# 20210419-JGaylord-doorman_adult_rig.net
KiCad netlist of a schematic drawn in EAGLE
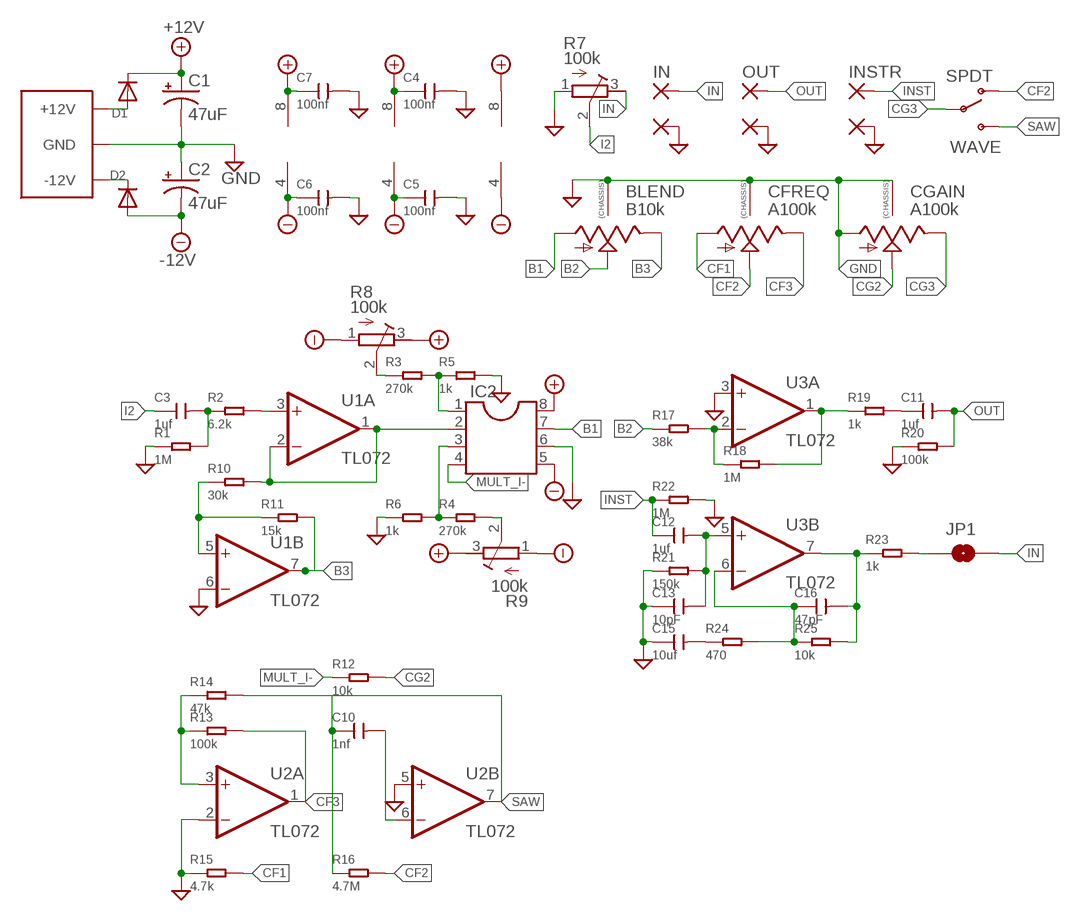
[diagram p0: schematic, sheet 1]

(export (version "E")
  (design (tool "Eeschema 10.0.6"))
  (components
    (comp (ref "BLEND")
      (value "B10k")
      (footprint "eagle-import:9MM_SNAP-IN_POT")
      (libsource (lib "eagle-import") (part "9MM_SNAP-IN_POT_CHASSIS"))
    )
    (comp (ref "C1")
      (value "47uF")
      (footprint "eagle-import:PAN_B_SMD+THRU")
      (libsource (lib "eagle-import") (part "CAP_SMD+THRUPAN_B"))
    )
    (comp (ref "C2")
      (value "47uF")
      (footprint "eagle-import:PAN_B_SMD+THRU")
      (libsource (lib "eagle-import") (part "CAP_SMD+THRUPAN_B"))
    )
    (comp (ref "C3")
      (value "1uf")
      (footprint "eagle-import:C1206")
      (fields (field (name "MPN") "CC1206KKX5R8BB106"))
      (libsource (lib "eagle-import") (part "CERAMIC-10UF-25V-10%-X5R(1206)"))
    )
    (comp (ref "C4")
      (value "100nf")
      (footprint "eagle-import:C0805")
      (fields (field (name "MPN") "CC0805KRX7R9BB104"))
      (libsource (lib "eagle-import") (part "CERAMIC-100NF-50V-10%-X7R(0805)"))
    )
    (comp (ref "C5")
      (value "100nf")
      (footprint "eagle-import:C0805")
      (fields (field (name "MPN") "CC0805KRX7R9BB104"))
      (libsource (lib "eagle-import") (part "CERAMIC-100NF-50V-10%-X7R(0805)"))
    )
    (comp (ref "C6")
      (value "100nf")
      (footprint "eagle-import:C0805")
      (fields (field (name "MPN") "CC0805KRX7R9BB104"))
      (libsource (lib "eagle-import") (part "CERAMIC-100NF-50V-10%-X7R(0805)"))
    )
    (comp (ref "C7")
      (value "100nf")
      (footprint "eagle-import:C0805")
      (fields (field (name "MPN") "CC0805KRX7R9BB104"))
      (libsource (lib "eagle-import") (part "CERAMIC-100NF-50V-10%-X7R(0805)"))
    )
    (comp (ref "C10")
      (value "1nf")
      (footprint "eagle-import:C0805")
      (fields (field (name "MPN") "CC0805KRX7R9BB104"))
      (libsource (lib "eagle-import") (part "CERAMIC-100NF-50V-10%-X7R(0805)"))
    )
    (comp (ref "C11")
      (value "1uf")
      (footprint "eagle-import:C1206")
      (fields (field (name "MPN") "CC1206KKX5R8BB106"))
      (libsource (lib "eagle-import") (part "CERAMIC-10UF-25V-10%-X5R(1206)"))
    )
    (comp (ref "C12")
      (value "1uf")
      (footprint "eagle-import:C1206")
      (fields (field (name "MPN") "CC1206KKX5R8BB106"))
      (libsource (lib "eagle-import") (part "CERAMIC-10UF-25V-10%-X5R(1206)"))
    )
    (comp (ref "C13")
      (value "10pF")
      (footprint "eagle-import:C0805")
      (fields (field (name "MPN") "CC0805KRX7R9BB104"))
      (libsource (lib "eagle-import") (part "CERAMIC-100NF-50V-10%-X7R(0805)"))
    )
    (comp (ref "C15")
      (value "10uf")
      (footprint "eagle-import:C1206")
      (fields (field (name "MPN") "CC1206KKX5R8BB106"))
      (libsource (lib "eagle-import") (part "CERAMIC-10UF-25V-10%-X5R(1206)"))
    )
    (comp (ref "C16")
      (value "47pF")
      (footprint "eagle-import:C0805")
      (fields (field (name "MPN") "CC0805KRX7R9BB104"))
      (libsource (lib "eagle-import") (part "CERAMIC-100NF-50V-10%-X7R(0805)"))
    )
    (comp (ref "CFREQ")
      (value "A100k")
      (footprint "eagle-import:9MM_SNAP-IN_POT")
      (libsource (lib "eagle-import") (part "9MM_SNAP-IN_POT_CHASSIS"))
    )
    (comp (ref "CGAIN")
      (value "A100k")
      (footprint "eagle-import:9MM_SNAP-IN_POT")
      (libsource (lib "eagle-import") (part "9MM_SNAP-IN_POT_CHASSIS"))
    )
    (comp (ref "D1")
      (value "DIODESOD-123")
      (footprint "eagle-import:SOD-123")
      (libsource (lib "eagle-import") (part "DIODESOD-123"))
    )
    (comp (ref "D2")
      (value "DIODESOD-123")
      (footprint "eagle-import:SOD-123")
      (libsource (lib "eagle-import") (part "DIODESOD-123"))
    )
    (comp (ref "GND")
      (value "WIREPAD1,6/0,9")
      (footprint "eagle-import:1,6_0,9")
      (libsource (lib "eagle-import") (part "WIREPAD1,6/0,9"))
    )
    (comp (ref "GND1")
      (value "WIREPAD1,6/0,9")
      (footprint "eagle-import:1,6_0,9")
      (libsource (lib "eagle-import") (part "WIREPAD1,6/0,9"))
    )
    (comp (ref "GND2")
      (value "WIREPAD1,6/0,9")
      (footprint "eagle-import:1,6_0,9")
      (libsource (lib "eagle-import") (part "WIREPAD1,6/0,9"))
    )
    (comp (ref "IC2")
      (value "DIL8")
      (footprint "eagle-import:DIL08")
      (libsource (lib "eagle-import") (part "DIL8"))
    )
    (comp (ref "IN")
      (value "WIREPAD1,6/0,9")
      (footprint "eagle-import:1,6_0,9")
      (libsource (lib "eagle-import") (part "WIREPAD1,6/0,9"))
    )
    (comp (ref "INSTR")
      (value "WIREPAD1,6/0,9")
      (footprint "eagle-import:1,6_0,9")
      (libsource (lib "eagle-import") (part "WIREPAD1,6/0,9"))
    )
    (comp (ref "JP1")
      (value "JUMPER-SMT_2_NO_NO-SILK")
      (footprint "eagle-import:SMT-JUMPER_2_NO_NO-SILK")
      (libsource (lib "eagle-import") (part "JUMPER-SMT_2_NO_NO-SILK"))
    )
    (comp (ref "OUT")
      (value "WIREPAD1,6/0,9")
      (footprint "eagle-import:1,6_0,9")
      (libsource (lib "eagle-import") (part "WIREPAD1,6/0,9"))
    )
    (comp (ref "R1")
      (value "1M")
      (footprint "eagle-import:R0805")
      (fields (field (name "MPN") "RC0805JR-071KL"))
      (libsource (lib "eagle-import") (part "SMD-RES-1K-5%-1/8W(0805)"))
    )
    (comp (ref "R2")
      (value "6.2k")
      (footprint "eagle-import:R0805")
      (fields (field (name "MPN") "RC0805JR-071KL"))
      (libsource (lib "eagle-import") (part "SMD-RES-1K-5%-1/8W(0805)"))
    )
    (comp (ref "R3")
      (value "270k")
      (footprint "eagle-import:R0805")
      (fields (field (name "MPN") "RC0805JR-071KL"))
      (libsource (lib "eagle-import") (part "SMD-RES-1K-5%-1/8W(0805)"))
    )
    (comp (ref "R4")
      (value "270k")
      (footprint "eagle-import:R0805")
      (fields (field (name "MPN") "RC0805JR-071KL"))
      (libsource (lib "eagle-import") (part "SMD-RES-1K-5%-1/8W(0805)"))
    )
    (comp (ref "R5")
      (value "1k")
      (footprint "eagle-import:R0805")
      (fields (field (name "MPN") "RC0805JR-071KL"))
      (libsource (lib "eagle-import") (part "SMD-RES-1K-5%-1/8W(0805)"))
    )
    (comp (ref "R6")
      (value "1k")
      (footprint "eagle-import:R0805")
      (fields (field (name "MPN") "RC0805JR-071KL"))
      (libsource (lib "eagle-import") (part "SMD-RES-1K-5%-1/8W(0805)"))
    )
    (comp (ref "R7")
      (value "100k")
      (footprint "eagle-import:RTRIM3224W")
      (libsource (lib "eagle-import") (part "R-TRIMM3224W"))
    )
    (comp (ref "R8")
      (value "100k")
      (footprint "eagle-import:RTRIM3224W")
      (libsource (lib "eagle-import") (part "R-TRIMM3224W"))
    )
    (comp (ref "R9")
      (value "100k")
      (footprint "eagle-import:RTRIM3224W")
      (libsource (lib "eagle-import") (part "R-TRIMM3224W"))
    )
    (comp (ref "R10")
      (value "30k")
      (footprint "eagle-import:R0805")
      (fields (field (name "MPN") "RC0805JR-071KL"))
      (libsource (lib "eagle-import") (part "SMD-RES-1K-5%-1/8W(0805)"))
    )
    (comp (ref "R11")
      (value "15k")
      (footprint "eagle-import:R0805")
      (fields (field (name "MPN") "RC0805JR-071KL"))
      (libsource (lib "eagle-import") (part "SMD-RES-1K-5%-1/8W(0805)"))
    )
    (comp (ref "R12")
      (value "10k")
      (footprint "eagle-import:R0805")
      (fields (field (name "MPN") "RC0805JR-071KL"))
      (libsource (lib "eagle-import") (part "SMD-RES-1K-5%-1/8W(0805)"))
    )
    (comp (ref "R13")
      (value "100k")
      (footprint "eagle-import:R0805")
      (fields (field (name "MPN") "RC0805JR-071KL"))
      (libsource (lib "eagle-import") (part "SMD-RES-1K-5%-1/8W(0805)"))
    )
    (comp (ref "R14")
      (value "47k")
      (footprint "eagle-import:R0805")
      (fields (field (name "MPN") "RC0805JR-071KL"))
      (libsource (lib "eagle-import") (part "SMD-RES-1K-5%-1/8W(0805)"))
    )
    (comp (ref "R15")
      (value "4.7k")
      (footprint "eagle-import:R0805")
      (fields (field (name "MPN") "RC0805JR-071KL"))
      (libsource (lib "eagle-import") (part "SMD-RES-1K-5%-1/8W(0805)"))
    )
    (comp (ref "R16")
      (value "4.7M")
      (footprint "eagle-import:R0805")
      (fields (field (name "MPN") "RC0805JR-071KL"))
      (libsource (lib "eagle-import") (part "SMD-RES-1K-5%-1/8W(0805)"))
    )
    (comp (ref "R17")
      (value "38k")
      (footprint "eagle-import:R0805")
      (fields (field (name "MPN") "RC0805JR-071KL"))
      (libsource (lib "eagle-import") (part "SMD-RES-1K-5%-1/8W(0805)"))
    )
    (comp (ref "R18")
      (value "1M")
      (footprint "eagle-import:R0805")
      (fields (field (name "MPN") "RC0805JR-071KL"))
      (libsource (lib "eagle-import") (part "SMD-RES-1K-5%-1/8W(0805)"))
    )
    (comp (ref "R19")
      (value "1k")
      (footprint "eagle-import:R0805")
      (fields (field (name "MPN") "RC0805JR-071KL"))
      (libsource (lib "eagle-import") (part "SMD-RES-1K-5%-1/8W(0805)"))
    )
    (comp (ref "R20")
      (value "100k")
      (footprint "eagle-import:R0805")
      (fields (field (name "MPN") "RC0805JR-071KL"))
      (libsource (lib "eagle-import") (part "SMD-RES-1K-5%-1/8W(0805)"))
    )
    (comp (ref "R21")
      (value "150k")
      (footprint "eagle-import:R0805")
      (fields (field (name "MPN") "RC0805JR-071KL"))
      (libsource (lib "eagle-import") (part "SMD-RES-1K-5%-1/8W(0805)"))
    )
    (comp (ref "R22")
      (value "1M")
      (footprint "eagle-import:R0805")
      (fields (field (name "MPN") "RC0805JR-071KL"))
      (libsource (lib "eagle-import") (part "SMD-RES-1K-5%-1/8W(0805)"))
    )
    (comp (ref "R23")
      (value "1k")
      (footprint "eagle-import:R0805")
      (fields (field (name "MPN") "RC0805JR-071KL"))
      (libsource (lib "eagle-import") (part "SMD-RES-1K-5%-1/8W(0805)"))
    )
    (comp (ref "R24")
      (value "470")
      (footprint "eagle-import:R0805")
      (fields (field (name "MPN") "RC0805JR-071KL"))
      (libsource (lib "eagle-import") (part "SMD-RES-1K-5%-1/8W(0805)"))
    )
    (comp (ref "R25")
      (value "10k")
      (footprint "eagle-import:R0805")
      (fields (field (name "MPN") "RC0805JR-071KL"))
      (libsource (lib "eagle-import") (part "SMD-RES-1K-5%-1/8W(0805)"))
    )
    (comp (ref "U$1")
      (value "EURO_POWER_LOCK")
      (footprint "eagle-import:EURO_PWR_HEADER_LOCK")
      (libsource (lib "eagle-import") (part "EURO_POWER_LOCK"))
    )
    (comp (ref "U1")
      (value "TL072")
      (footprint "eagle-import:TSSOP-8")
      (libsource (lib "eagle-import") (part "TL072TSSOP"))
    )
    (comp (ref "U2")
      (value "TL072")
      (footprint "eagle-import:TSSOP-8")
      (libsource (lib "eagle-import") (part "TL072TSSOP"))
    )
    (comp (ref "U3")
      (value "TL072")
      (footprint "eagle-import:TSSOP-8")
      (libsource (lib "eagle-import") (part "TL072TSSOP"))
    )
    (comp (ref "WAVE")
      (value "SPDT")
      (footprint "eagle-import:SUBMINI_TOGGLE")
      (libsource (lib "eagle-import") (part "SUBMINI_SPDT"))
    )
  )
  (nets
    (net (code "1") (name "+12V") (class "Default")
      (node (ref "C1") (pin "+") (pinfunction "+_+") (pintype "passive"))
      (node (ref "C1") (pin "++") (pinfunction "+_++") (pintype "passive"))
      (node (ref "C4") (pin "1") (pinfunction "1_1") (pintype "passive"))
      (node (ref "C7") (pin "1") (pinfunction "1_1") (pintype "passive"))
      (node (ref "D1") (pin "C") (pinfunction "C_C") (pintype "passive"))
      (node (ref "IC2") (pin "8") (pinfunction "8_8") (pintype "passive"))
      (node (ref "R8") (pin "3") (pinfunction "E_3") (pintype "passive"))
      (node (ref "R9") (pin "3") (pinfunction "E_3") (pintype "passive"))
      (node (ref "U1") (pin "8") (pinfunction "V+_8") (pintype "power_in"))
      (node (ref "U2") (pin "8") (pinfunction "V+_8") (pintype "power_in"))
      (node (ref "U3") (pin "8") (pinfunction "V+_8") (pintype "power_in"))
    )
    (net (code "2") (name "-12V") (class "Default")
      (node (ref "C2") (pin "-") (pinfunction "-_-") (pintype "passive"))
      (node (ref "C2") (pin "--") (pinfunction "-_--") (pintype "passive"))
      (node (ref "C5") (pin "1") (pinfunction "1_1") (pintype "passive"))
      (node (ref "C6") (pin "1") (pinfunction "1_1") (pintype "passive"))
      (node (ref "D2") (pin "A") (pinfunction "A_A") (pintype "passive"))
      (node (ref "IC2") (pin "5") (pinfunction "5_5") (pintype "passive"))
      (node (ref "R8") (pin "1") (pinfunction "A_1") (pintype "passive"))
      (node (ref "R9") (pin "1") (pinfunction "A_1") (pintype "passive"))
      (node (ref "U1") (pin "4") (pinfunction "V-_4") (pintype "power_in"))
      (node (ref "U2") (pin "4") (pinfunction "V-_4") (pintype "power_in"))
      (node (ref "U3") (pin "4") (pinfunction "V-_4") (pintype "power_in"))
    )
    (net (code "3") (name "B1") (class "Default")
      (node (ref "BLEND") (pin "1") (pinfunction "A_1") (pintype "passive"))
      (node (ref "IC2") (pin "7") (pinfunction "7_7") (pintype "passive"))
    )
    (net (code "4") (name "B2") (class "Default")
      (node (ref "BLEND") (pin "2") (pinfunction "S_2") (pintype "passive"))
      (node (ref "R17") (pin "1") (pinfunction "1_1") (pintype "passive"))
    )
    (net (code "5") (name "B3") (class "Default")
      (node (ref "BLEND") (pin "3") (pinfunction "E_3") (pintype "passive"))
      (node (ref "R11") (pin "2") (pinfunction "2_2") (pintype "passive"))
      (node (ref "U1") (pin "7") (pinfunction "OUT_7") (pintype "output"))
    )
    (net (code "6") (name "CF1") (class "Default")
      (node (ref "CFREQ") (pin "1") (pinfunction "A_1") (pintype "passive"))
      (node (ref "R15") (pin "2") (pinfunction "2_2") (pintype "passive"))
    )
    (net (code "7") (name "CF2") (class "Default")
      (node (ref "CFREQ") (pin "2") (pinfunction "S_2") (pintype "passive"))
      (node (ref "R16") (pin "2") (pinfunction "2_2") (pintype "passive"))
      (node (ref "WAVE") (pin "1") (pinfunction "O_1") (pintype "passive"))
    )
    (net (code "8") (name "CF3") (class "Default")
      (node (ref "CFREQ") (pin "3") (pinfunction "E_3") (pintype "passive"))
      (node (ref "R13") (pin "2") (pinfunction "2_2") (pintype "passive"))
      (node (ref "U2") (pin "1") (pinfunction "OUT_1") (pintype "output"))
    )
    (net (code "9") (name "CG2") (class "Default")
      (node (ref "CGAIN") (pin "2") (pinfunction "S_2") (pintype "passive"))
      (node (ref "R12") (pin "2") (pinfunction "2_2") (pintype "passive"))
    )
    (net (code "10") (name "CG3") (class "Default")
      (node (ref "CGAIN") (pin "3") (pinfunction "E_3") (pintype "passive"))
      (node (ref "WAVE") (pin "COM") (pinfunction "COMMON_COM") (pintype "passive"))
    )
    (net (code "11") (name "GND") (class "Default")
      (node (ref "BLEND") (pin "CHASSIS1") (pinfunction "P$1_CHASSIS1") (pintype "passive"))
      (node (ref "BLEND") (pin "CHASSIS2") (pinfunction "P$1_CHASSIS2") (pintype "passive"))
      (node (ref "C1") (pin "-") (pinfunction "-_-") (pintype "passive"))
      (node (ref "C1") (pin "--") (pinfunction "-_--") (pintype "passive"))
      (node (ref "C13") (pin "1") (pinfunction "1_1") (pintype "passive"))
      (node (ref "C15") (pin "1") (pinfunction "1_1") (pintype "passive"))
      (node (ref "C2") (pin "+") (pinfunction "+_+") (pintype "passive"))
      (node (ref "C2") (pin "++") (pinfunction "+_++") (pintype "passive"))
      (node (ref "C4") (pin "2") (pinfunction "2_2") (pintype "passive"))
      (node (ref "C5") (pin "2") (pinfunction "2_2") (pintype "passive"))
      (node (ref "C6") (pin "2") (pinfunction "2_2") (pintype "passive"))
      (node (ref "C7") (pin "2") (pinfunction "2_2") (pintype "passive"))
      (node (ref "CFREQ") (pin "CHASSIS1") (pinfunction "P$1_CHASSIS1") (pintype "passive"))
      (node (ref "CFREQ") (pin "CHASSIS2") (pinfunction "P$1_CHASSIS2") (pintype "passive"))
      (node (ref "CGAIN") (pin "1") (pinfunction "A_1") (pintype "passive"))
      (node (ref "CGAIN") (pin "CHASSIS1") (pinfunction "P$1_CHASSIS1") (pintype "passive"))
      (node (ref "CGAIN") (pin "CHASSIS2") (pinfunction "P$1_CHASSIS2") (pintype "passive"))
      (node (ref "GND") (pin "1") (pinfunction "P_1") (pintype "passive"))
      (node (ref "GND1") (pin "1") (pinfunction "P_1") (pintype "passive"))
      (node (ref "GND2") (pin "1") (pinfunction "P_1") (pintype "passive"))
      (node (ref "IC2") (pin "6") (pinfunction "6_6") (pintype "passive"))
      (node (ref "R1") (pin "1") (pinfunction "1_1") (pintype "passive"))
      (node (ref "R15") (pin "1") (pinfunction "1_1") (pintype "passive"))
      (node (ref "R20") (pin "1") (pinfunction "1_1") (pintype "passive"))
      (node (ref "R21") (pin "1") (pinfunction "1_1") (pintype "passive"))
      (node (ref "R22") (pin "2") (pinfunction "2_2") (pintype "passive"))
      (node (ref "R5") (pin "2") (pinfunction "2_2") (pintype "passive"))
      (node (ref "R6") (pin "1") (pinfunction "1_1") (pintype "passive"))
      (node (ref "R7") (pin "1") (pinfunction "A_1") (pintype "passive"))
      (node (ref "U$1") (pin "GND1") (pinfunction "GND_GND1") (pintype "bidirectional"))
      (node (ref "U$1") (pin "GND2") (pinfunction "GND_GND2") (pintype "bidirectional"))
      (node (ref "U$1") (pin "GND3") (pinfunction "GND_GND3") (pintype "bidirectional"))
      (node (ref "U$1") (pin "GND4") (pinfunction "GND_GND4") (pintype "bidirectional"))
      (node (ref "U$1") (pin "GND5") (pinfunction "GND_GND5") (pintype "bidirectional"))
      (node (ref "U$1") (pin "GND6") (pinfunction "GND_GND6") (pintype "bidirectional"))
      (node (ref "U1") (pin "6") (pinfunction "-IN_6") (pintype "input"))
      (node (ref "U2") (pin "2") (pinfunction "-IN_2") (pintype "input"))
      (node (ref "U2") (pin "5") (pinfunction "+IN_5") (pintype "input"))
      (node (ref "U3") (pin "3") (pinfunction "+IN_3") (pintype "input"))
    )
    (net (code "12") (name "I2") (class "Default")
      (node (ref "C3") (pin "1") (pinfunction "1_1") (pintype "passive"))
      (node (ref "R7") (pin "2") (pinfunction "S_2") (pintype "passive"))
    )
    (net (code "13") (name "IN") (class "Default")
      (node (ref "IN") (pin "1") (pinfunction "P_1") (pintype "passive"))
      (node (ref "JP1") (pin "2") (pinfunction "2_2") (pintype "passive"))
      (node (ref "R7") (pin "3") (pinfunction "E_3") (pintype "passive"))
    )
    (net (code "14") (name "INST") (class "Default")
      (node (ref "C12") (pin "1") (pinfunction "1_1") (pintype "passive"))
      (node (ref "INSTR") (pin "1") (pinfunction "P_1") (pintype "passive"))
      (node (ref "R22") (pin "1") (pinfunction "1_1") (pintype "passive"))
    )
    (net (code "15") (name "MULT_I-") (class "Default")
      (node (ref "IC2") (pin "4") (pinfunction "4_4") (pintype "passive"))
      (node (ref "R12") (pin "1") (pinfunction "1_1") (pintype "passive"))
    )
    (net (code "16") (name "Net-(C3-Pad2)") (class "Default")
      (node (ref "C3") (pin "2") (pinfunction "2_2") (pintype "passive"))
      (node (ref "R1") (pin "2") (pinfunction "2_2") (pintype "passive"))
      (node (ref "R2") (pin "1") (pinfunction "1_1") (pintype "passive"))
    )
    (net (code "17") (name "Net-(C11-Pad1)") (class "Default")
      (node (ref "C11") (pin "1") (pinfunction "1_1") (pintype "passive"))
      (node (ref "R19") (pin "2") (pinfunction "2_2") (pintype "passive"))
    )
    (net (code "18") (name "Net-(C15-Pad2)") (class "Default")
      (node (ref "C15") (pin "2") (pinfunction "2_2") (pintype "passive"))
      (node (ref "R24") (pin "1") (pinfunction "1_1") (pintype "passive"))
    )
    (net (code "19") (name "Net-(D1-PadA)") (class "Default")
      (node (ref "D1") (pin "A") (pinfunction "A_A") (pintype "passive"))
      (node (ref "U$1") (pin "POS1") (pinfunction "+12V_POS1") (pintype "bidirectional"))
      (node (ref "U$1") (pin "POS2") (pinfunction "+12V_POS2") (pintype "bidirectional"))
    )
    (net (code "20") (name "Net-(D2-PadC)") (class "Default")
      (node (ref "D2") (pin "C") (pinfunction "C_C") (pintype "passive"))
      (node (ref "U$1") (pin "NEG1") (pinfunction "-12V_NEG1") (pintype "bidirectional"))
      (node (ref "U$1") (pin "NEG2") (pinfunction "-12V_NEG2") (pintype "bidirectional"))
    )
    (net (code "21") (name "Net-(IC2-Pad1)") (class "Default")
      (node (ref "IC2") (pin "1") (pinfunction "1_1") (pintype "passive"))
      (node (ref "R3") (pin "2") (pinfunction "2_2") (pintype "passive"))
      (node (ref "R5") (pin "1") (pinfunction "1_1") (pintype "passive"))
    )
    (net (code "22") (name "Net-(IC2-Pad3)") (class "Default")
      (node (ref "IC2") (pin "3") (pinfunction "3_3") (pintype "passive"))
      (node (ref "R4") (pin "1") (pinfunction "1_1") (pintype "passive"))
      (node (ref "R6") (pin "2") (pinfunction "2_2") (pintype "passive"))
    )
    (net (code "23") (name "Net-(JP1-Pad1)") (class "Default")
      (node (ref "JP1") (pin "1") (pinfunction "1_1") (pintype "passive"))
      (node (ref "R23") (pin "2") (pinfunction "2_2") (pintype "passive"))
    )
    (net (code "24") (name "Net-(R8-S)") (class "Default")
      (node (ref "R3") (pin "1") (pinfunction "1_1") (pintype "passive"))
      (node (ref "R8") (pin "2") (pinfunction "S_2") (pintype "passive"))
    )
    (net (code "25") (name "Net-(R9-S)") (class "Default")
      (node (ref "R4") (pin "2") (pinfunction "2_2") (pintype "passive"))
      (node (ref "R9") (pin "2") (pinfunction "S_2") (pintype "passive"))
    )
    (net (code "26") (name "Net-(U1A-+IN)") (class "Default")
      (node (ref "R2") (pin "2") (pinfunction "2_2") (pintype "passive"))
      (node (ref "U1") (pin "3") (pinfunction "+IN_3") (pintype "input"))
    )
    (net (code "27") (name "Net-(U1A--IN)") (class "Default")
      (node (ref "IC2") (pin "2") (pinfunction "2_2") (pintype "passive"))
      (node (ref "R10") (pin "2") (pinfunction "2_2") (pintype "passive"))
      (node (ref "U1") (pin "1") (pinfunction "OUT_1") (pintype "output"))
      (node (ref "U1") (pin "2") (pinfunction "-IN_2") (pintype "input"))
    )
    (net (code "28") (name "Net-(U1B-+IN)") (class "Default")
      (node (ref "R10") (pin "1") (pinfunction "1_1") (pintype "passive"))
      (node (ref "R11") (pin "1") (pinfunction "1_1") (pintype "passive"))
      (node (ref "U1") (pin "5") (pinfunction "+IN_5") (pintype "input"))
    )
    (net (code "29") (name "Net-(U2A-+IN)") (class "Default")
      (node (ref "R13") (pin "1") (pinfunction "1_1") (pintype "passive"))
      (node (ref "R14") (pin "1") (pinfunction "1_1") (pintype "passive"))
      (node (ref "U2") (pin "3") (pinfunction "+IN_3") (pintype "input"))
    )
    (net (code "30") (name "Net-(U2B--IN)") (class "Default")
      (node (ref "C10") (pin "2") (pinfunction "2_2") (pintype "passive"))
      (node (ref "U2") (pin "6") (pinfunction "-IN_6") (pintype "input"))
    )
    (net (code "31") (name "Net-(U3A--IN)") (class "Default")
      (node (ref "R17") (pin "2") (pinfunction "2_2") (pintype "passive"))
      (node (ref "R18") (pin "1") (pinfunction "1_1") (pintype "passive"))
      (node (ref "U3") (pin "2") (pinfunction "-IN_2") (pintype "input"))
    )
    (net (code "32") (name "Net-(U3A-OUT)") (class "Default")
      (node (ref "R18") (pin "2") (pinfunction "2_2") (pintype "passive"))
      (node (ref "R19") (pin "1") (pinfunction "1_1") (pintype "passive"))
      (node (ref "U3") (pin "1") (pinfunction "OUT_1") (pintype "output"))
    )
    (net (code "33") (name "Net-(U3B-+IN)") (class "Default")
      (node (ref "C12") (pin "2") (pinfunction "2_2") (pintype "passive"))
      (node (ref "C13") (pin "2") (pinfunction "2_2") (pintype "passive"))
      (node (ref "R21") (pin "2") (pinfunction "2_2") (pintype "passive"))
      (node (ref "U3") (pin "5") (pinfunction "+IN_5") (pintype "input"))
    )
    (net (code "34") (name "Net-(U3B--IN)") (class "Default")
      (node (ref "C16") (pin "1") (pinfunction "1_1") (pintype "passive"))
      (node (ref "R24") (pin "2") (pinfunction "2_2") (pintype "passive"))
      (node (ref "R25") (pin "1") (pinfunction "1_1") (pintype "passive"))
      (node (ref "U3") (pin "6") (pinfunction "-IN_6") (pintype "input"))
    )
    (net (code "35") (name "Net-(U3B-OUT)") (class "Default")
      (node (ref "C16") (pin "2") (pinfunction "2_2") (pintype "passive"))
      (node (ref "R23") (pin "1") (pinfunction "1_1") (pintype "passive"))
      (node (ref "R25") (pin "2") (pinfunction "2_2") (pintype "passive"))
      (node (ref "U3") (pin "7") (pinfunction "OUT_7") (pintype "output"))
    )
    (net (code "36") (name "OUT") (class "Default")
      (node (ref "C11") (pin "2") (pinfunction "2_2") (pintype "passive"))
      (node (ref "OUT") (pin "1") (pinfunction "P_1") (pintype "passive"))
      (node (ref "R20") (pin "2") (pinfunction "2_2") (pintype "passive"))
    )
    (net (code "37") (name "SAW") (class "Default")
      (node (ref "C10") (pin "1") (pinfunction "1_1") (pintype "passive"))
      (node (ref "R14") (pin "2") (pinfunction "2_2") (pintype "passive"))
      (node (ref "R16") (pin "1") (pinfunction "1_1") (pintype "passive"))
      (node (ref "U2") (pin "7") (pinfunction "OUT_7") (pintype "output"))
      (node (ref "WAVE") (pin "3") (pinfunction "S_3") (pintype "passive"))
    )
  )
)
